# ACS_SchDoc.net
KiCad netlist of a schematic drawn in Altium Designer
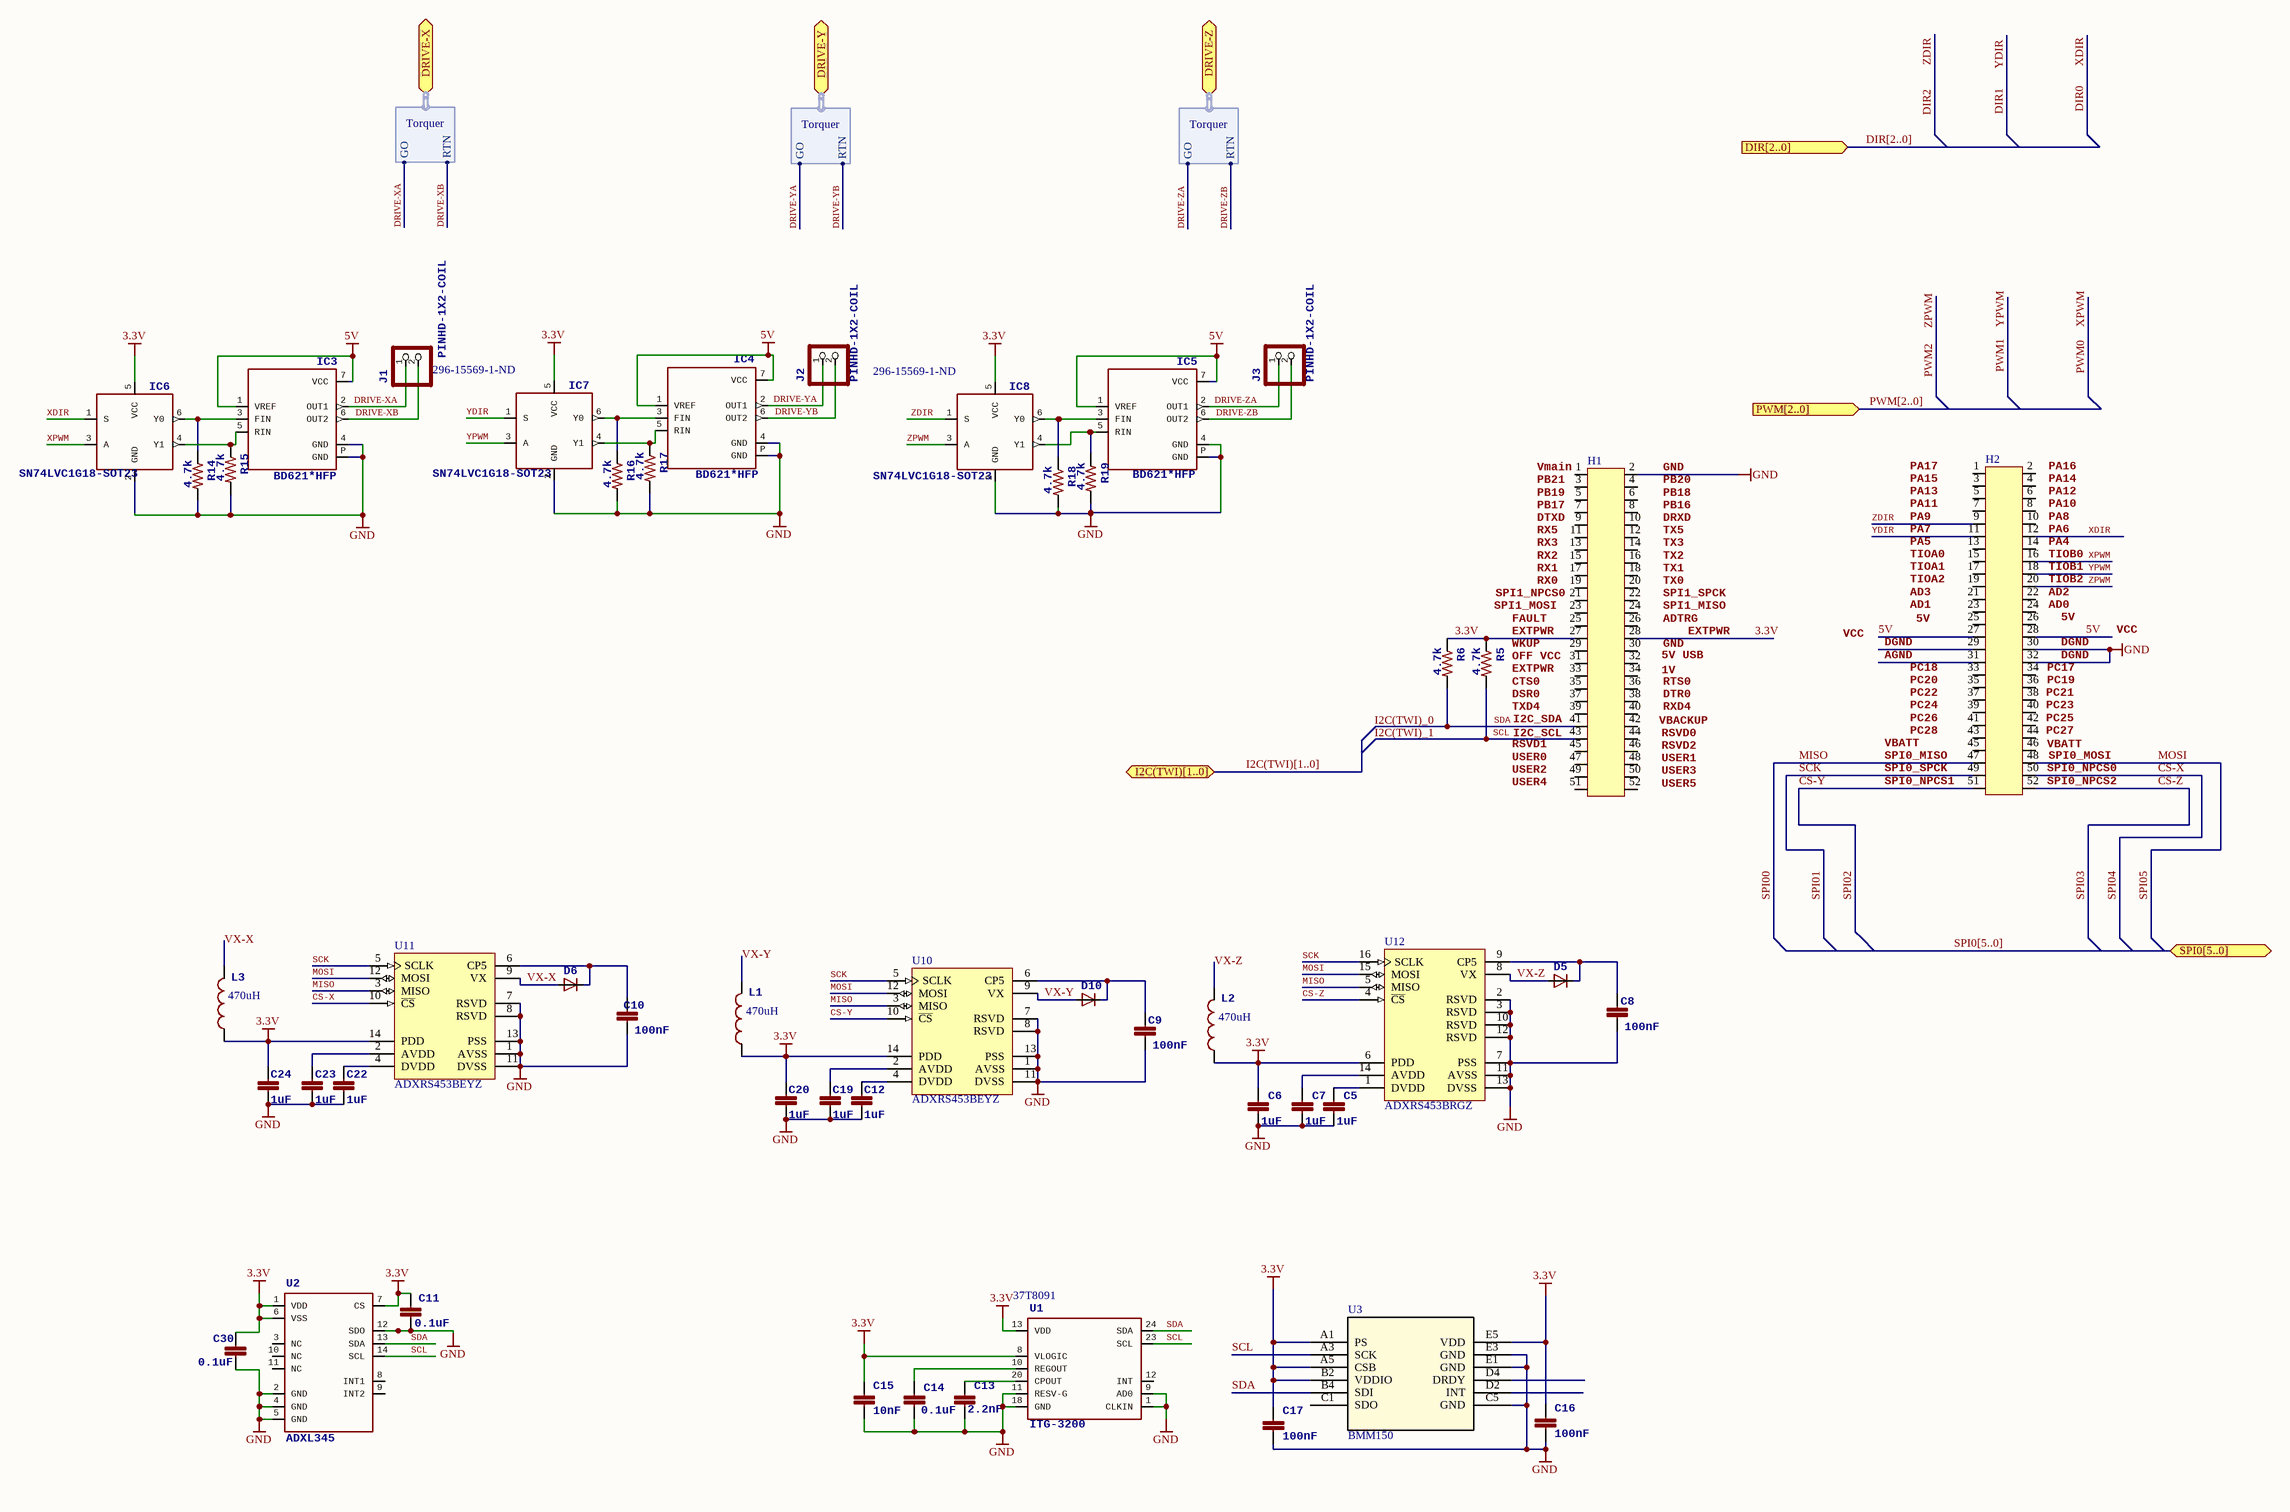
[diagram p0: ACS.SchDoc.SchDoc]

(export (version "E")
  (design (tool "Eeschema 10.0.6"))
  (components
    (comp (ref "C5")
      (value "1uF")
      (footprint "0603-CAP")
      (description "<b>Capacitor</b>\nStandard SMT, and 0.1\", and 0.2\" leaded ceramic capacitors")
      (libsource (lib "") (part "CAPACITOR-0603_1"))
    )
    (comp (ref "C6")
      (value "1uF")
      (footprint "0603-CAP")
      (description "<b>Capacitor</b>\nStandard SMT, and 0.1\", and 0.2\" leaded ceramic capacitors")
      (libsource (lib "") (part "CAPACITOR-0603_1"))
    )
    (comp (ref "C7")
      (value "1uF")
      (footprint "0603-CAP")
      (description "<b>Capacitor</b>\nStandard SMT, and 0.1\", and 0.2\" leaded ceramic capacitors")
      (libsource (lib "") (part "CAPACITOR-0603_1"))
    )
    (comp (ref "C8")
      (value "100nF")
      (footprint "0603-CAP")
      (description "<b>Capacitor</b>\nStandard SMT, and 0.1\", and 0.2\" leaded ceramic capacitors")
      (libsource (lib "urover") (part "CAPACITOR-0603"))
    )
    (comp (ref "C9")
      (value "100nF")
      (footprint "0603-CAP")
      (description "<b>Capacitor</b>\nStandard SMT, and 0.1\", and 0.2\" leaded ceramic capacitors")
      (libsource (lib "urover") (part "CAPACITOR-0603"))
    )
    (comp (ref "C10")
      (value "100nF")
      (footprint "0603-CAP")
      (description "<b>Capacitor</b>\nStandard SMT, and 0.1\", and 0.2\" leaded ceramic capacitors")
      (libsource (lib "urover") (part "CAPACITOR-0603"))
    )
    (comp (ref "C11")
      (value "0.1uF")
      (footprint "0603-CAP")
      (description "<b>Capacitor</b>\nStandard SMT, and 0.1\", and 0.2\" leaded ceramic capacitors")
      (libsource (lib "urover") (part "CAPACITOR-0603"))
    )
    (comp (ref "C12")
      (value "1uF")
      (footprint "0603-CAP")
      (description "<b>Capacitor</b>\nStandard SMT, and 0.1\", and 0.2\" leaded ceramic capacitors")
      (libsource (lib "") (part "CAPACITOR-0603_1"))
    )
    (comp (ref "C13")
      (value "2.2nF")
      (footprint "0603-CAP")
      (description "<b>Capacitor</b>\nStandard SMT, and 0.1\", and 0.2\" leaded ceramic capacitors")
      (libsource (lib "urover") (part "CAPACITOR-0603"))
    )
    (comp (ref "C14")
      (value "0.1uF")
      (footprint "0603-CAP")
      (description "<b>Capacitor</b>\nStandard SMT, and 0.1\", and 0.2\" leaded ceramic capacitors")
      (libsource (lib "urover") (part "CAPACITOR-0603"))
    )
    (comp (ref "C15")
      (value "10nF")
      (footprint "0603-CAP")
      (description "<b>Capacitor</b>\nStandard SMT, and 0.1\", and 0.2\" leaded ceramic capacitors")
      (libsource (lib "urover") (part "CAPACITOR-0603"))
    )
    (comp (ref "C16") (value "100nF") (footprint "0603-CAP") (libsource (lib "ACS") (part "CAPACITOR-0603")))
    (comp (ref "C17") (value "100nF") (footprint "0603-CAP") (libsource (lib "ACS") (part "CAPACITOR-0603")))
    (comp (ref "C19")
      (value "1uF")
      (footprint "0603-CAP")
      (description "<b>Capacitor</b>\nStandard SMT, and 0.1\", and 0.2\" leaded ceramic capacitors")
      (libsource (lib "") (part "CAPACITOR-0603_1"))
    )
    (comp (ref "C20")
      (value "1uF")
      (footprint "0603-CAP")
      (description "<b>Capacitor</b>\nStandard SMT, and 0.1\", and 0.2\" leaded ceramic capacitors")
      (libsource (lib "") (part "CAPACITOR-0603_1"))
    )
    (comp (ref "C22")
      (value "1uF")
      (footprint "0603-CAP")
      (description "<b>Capacitor</b>\nStandard SMT, and 0.1\", and 0.2\" leaded ceramic capacitors")
      (libsource (lib "") (part "CAPACITOR-0603_1"))
    )
    (comp (ref "C23")
      (value "1uF")
      (footprint "0603-CAP")
      (description "<b>Capacitor</b>\nStandard SMT, and 0.1\", and 0.2\" leaded ceramic capacitors")
      (libsource (lib "") (part "CAPACITOR-0603_1"))
    )
    (comp (ref "C24")
      (value "1uF")
      (footprint "0603-CAP")
      (description "<b>Capacitor</b>\nStandard SMT, and 0.1\", and 0.2\" leaded ceramic capacitors")
      (libsource (lib "") (part "CAPACITOR-0603_1"))
    )
    (comp (ref "C30")
      (value "0.1uF")
      (footprint "0603-CAP")
      (description "<b>Capacitor</b>\nStandard SMT, and 0.1\", and 0.2\" leaded ceramic capacitors")
      (libsource (lib "urover") (part "CAPACITOR-0603"))
    )
    (comp (ref "D5")
      (value "<b>Diode</b>\nStandard reverse protection diodes and small signal diodes.")
      (footprint "DIODE-SMA")
      (libsource (lib "urover") (part "DIODE-SMA"))
    )
    (comp (ref "D6")
      (value "<b>Diode</b>\nStandard reverse protection diodes and small signal diodes.")
      (footprint "DIODE-SMA")
      (libsource (lib "urover") (part "DIODE-SMA"))
    )
    (comp (ref "D10")
      (value "<b>Diode</b>\nStandard reverse protection diodes and small signal diodes.")
      (footprint "DIODE-SMA")
      (libsource (lib "urover") (part "DIODE-SMA"))
    )
    (comp (ref "H1")
      (value "H?")
      (footprint "SAMTEC_ESQ_126_39_G_D")
      (description "26X2 header")
      (libsource (lib "SAMTEC_ESQ_126_39_G_D") (part "SAMTEC_ESQ_126_39_G_D"))
    )
    (comp (ref "H2")
      (value "H?")
      (footprint "SAMTEC_ESQ_126_39_G_D")
      (description "26X2 header")
      (libsource (lib "SAMTEC_ESQ_126_39_G_D") (part "SAMTEC_ESQ_126_39_G_D"))
    )
    (comp (ref "IC3")
      (value "BD621*HFP")
      (footprint "HRP7")
      (fields (field (name "MPN") "BD6232HFP-TR"))
      (libsource (lib "urover") (part "BD621*HFP"))
    )
    (comp (ref "IC4")
      (value "BD621*HFP")
      (footprint "HRP7")
      (fields (field (name "MPN") "BD6232HFP-TR"))
      (libsource (lib "urover") (part "BD621*HFP"))
    )
    (comp (ref "IC5")
      (value "BD621*HFP")
      (footprint "HRP7")
      (fields (field (name "MPN") "BD6232HFP-TR"))
      (libsource (lib "urover") (part "BD621*HFP"))
    )
    (comp (ref "IC6")
      (value "SN74LVC1G18-SOT23")
      (footprint "SOT23-6")
      (libsource (lib "urover") (part "SN74LVC1G18-SOT23"))
    )
    (comp (ref "IC7")
      (value "SN74LVC1G18-SOT23")
      (footprint "SOT23-6")
      (fields (field (name "SUPPLIER PART NUMBER 1") "296-15569-1-ND"))
      (libsource (lib "urover") (part "SN74LVC1G18-SOT23"))
    )
    (comp (ref "IC8")
      (value "SN74LVC1G18-SOT23")
      (footprint "SOT23-6")
      (fields (field (name "SUPPLIER PART NUMBER 1") "296-15569-1-ND"))
      (libsource (lib "urover") (part "SN74LVC1G18-SOT23"))
    )
    (comp (ref "J1")
      (value "PINHD-1X2-COIL")
      (footprint "HEADER-1X2-COIL")
      (libsource (lib "urover") (part "PINHD-1X2-COIL"))
    )
    (comp (ref "J2")
      (value "PINHD-1X2-COIL")
      (footprint "HEADER-1X2-COIL")
      (libsource (lib "urover") (part "PINHD-1X2-COIL"))
    )
    (comp (ref "J3")
      (value "PINHD-1X2-COIL")
      (footprint "HEADER-1X2-COIL")
      (libsource (lib "urover") (part "PINHD-1X2-COIL"))
    )
    (comp (ref "L1")
      (value "470uH")
      (footprint "1210")
      (fields (field (name "Comment") "<b>Inductors</b>"))
      (libsource (lib "urover") (part "INDUCTOR-1210_470uH"))
    )
    (comp (ref "L2")
      (value "470uH")
      (footprint "1210")
      (fields (field (name "Comment") "<b>Inductors</b>"))
      (libsource (lib "urover") (part "INDUCTOR-1210_470uH"))
    )
    (comp (ref "L3")
      (value "470uH")
      (footprint "1210")
      (fields (field (name "Comment") "Inductor"))
      (libsource (lib "urover") (part "INDUCTOR-1210_470uH"))
    )
    (comp (ref "R5")
      (value "4.7k")
      (footprint "0603-RES")
      (description "<p><b>Resistor</b></p>\nBasic schematic elements and footprints for resistors.")
      (libsource (lib "urover") (part "RESISTOR-0603"))
    )
    (comp (ref "R6")
      (value "4.7k")
      (footprint "0603-RES")
      (description "<p><b>Resistor</b></p>\nBasic schematic elements and footprints for resistors.")
      (libsource (lib "urover") (part "RESISTOR-0603"))
    )
    (comp (ref "R14")
      (value "4.7k")
      (footprint "0603-RES")
      (description "<p><b>Resistor</b></p>\nBasic schematic elements and footprints for resistors.")
      (libsource (lib "urover") (part "RESISTOR-0603"))
    )
    (comp (ref "R15")
      (value "4.7k")
      (footprint "0603-RES")
      (description "<p><b>Resistor</b></p>\nBasic schematic elements and footprints for resistors.")
      (libsource (lib "urover") (part "RESISTOR-0603"))
    )
    (comp (ref "R16")
      (value "4.7k")
      (footprint "0603-RES")
      (description "<p><b>Resistor</b></p>\nBasic schematic elements and footprints for resistors.")
      (libsource (lib "urover") (part "RESISTOR-0603"))
    )
    (comp (ref "R17")
      (value "4.7k")
      (footprint "0603-RES")
      (description "<p><b>Resistor</b></p>\nBasic schematic elements and footprints for resistors.")
      (libsource (lib "urover") (part "RESISTOR-0603"))
    )
    (comp (ref "R18")
      (value "4.7k")
      (footprint "0603-RES")
      (description "<p><b>Resistor</b></p>\nBasic schematic elements and footprints for resistors.")
      (libsource (lib "urover") (part "RESISTOR-0603"))
    )
    (comp (ref "R19")
      (value "4.7k")
      (footprint "0603-RES")
      (description "<p><b>Resistor</b></p>\nBasic schematic elements and footprints for resistors.")
      (libsource (lib "urover") (part "RESISTOR-0603"))
    )
    (comp (ref "U1")
      (value "ITG-3200")
      (footprint "QFN-24")
      (description "ITG-3200 3-axis gyro, digital output, qfn24 package")
      (fields (field (name "SUPPLIER PART NUMBER 1") "37T8091"))
      (libsource (lib "urover") (part "ITG-3200"))
    )
    (comp (ref "U2") (value "ADXL345") (footprint "LGA14") (libsource (lib "urover") (part "ADXL345")))
    (comp (ref "U3")
      (value "BMM150")
      (footprint "BGA_1590X1590")
      (description "Imported")
      (libsource (lib "BMM150") (part "BMM150"))
    )
    (comp (ref "U10")
      (value "ADXRS453BEYZ")
      (footprint "ADI-EY-14-1_V")
      (description "High Performance, Digital Output Gyroscope with SPI, 77.5 Hz BW, Industrial, 14-pin LCC, Tube")
      (fields (field (name "MANUFACTURER") "Analog Devices"))
      (libsource (lib "Altium Content Vault") (part "ADI-ADXRS453-EY-14-1"))
    )
    (comp (ref "U11")
      (value "ADXRS453BEYZ")
      (footprint "ADI-EY-14-1_V")
      (description "High Performance, Digital Output Gyroscope with SPI, 77.5 Hz BW, Industrial, 14-pin LCC, Tube")
      (fields (field (name "MANUFACTURER") "Analog Devices"))
      (libsource (lib "Altium Content Vault") (part "ADI-ADXRS453-EY-14-1"))
    )
    (comp (ref "U12")
      (value "ADXRS453BRGZ")
      (footprint "ADI-RG-16-1_M")
      (description "High Performance, Digital Output Gyroscope with SPI, 77.5 Hz BW, Industrial, 16-pin SOIC, Tube")
      (fields (field (name "MANUFACTURER") "Analog Devices"))
      (libsource (lib "Altium Content Vault") (part "ADI-ADXRS453-RG-16-1"))
    )
  )
  (nets
    (net (code "4") (name "/DIR0") (class "Default")
      (node (ref "H2") (pin "12") (pinfunction "12_12") (pintype "passive"))
      (node (ref "IC6") (pin "1") (pinfunction "S_1") (pintype "passive"))
    )
    (net (code "5") (name "/DIR1") (class "Default")
      (node (ref "H2") (pin "11") (pinfunction "11_11") (pintype "passive"))
      (node (ref "IC7") (pin "1") (pinfunction "S_1") (pintype "passive"))
    )
    (net (code "6") (name "/DIR2") (class "Default")
      (node (ref "H2") (pin "9") (pinfunction "9_9") (pintype "passive"))
      (node (ref "IC8") (pin "1") (pinfunction "S_1") (pintype "passive"))
    )
    (net (code "8") (name "/DRIVE-XA") (class "Default")
      (node (ref "IC3") (pin "2") (pinfunction "OUT1_2") (pintype "output"))
      (node (ref "J1") (pin "1") (pinfunction "1_1") (pintype "passive"))
    )
    (net (code "9") (name "/DRIVE-XB") (class "Default")
      (node (ref "IC3") (pin "6") (pinfunction "OUT2_6") (pintype "output"))
      (node (ref "J1") (pin "2") (pinfunction "2_2") (pintype "passive"))
    )
    (net (code "10") (name "/DRIVE-YA") (class "Default")
      (node (ref "IC4") (pin "2") (pinfunction "OUT1_2") (pintype "output"))
      (node (ref "J2") (pin "1") (pinfunction "1_1") (pintype "passive"))
    )
    (net (code "11") (name "/DRIVE-YB") (class "Default")
      (node (ref "IC4") (pin "6") (pinfunction "OUT2_6") (pintype "output"))
      (node (ref "J2") (pin "2") (pinfunction "2_2") (pintype "passive"))
    )
    (net (code "12") (name "/DRIVE-ZA") (class "Default")
      (node (ref "IC5") (pin "2") (pinfunction "OUT1_2") (pintype "output"))
      (node (ref "J3") (pin "1") (pinfunction "1_1") (pintype "passive"))
    )
    (net (code "13") (name "/DRIVE-ZB") (class "Default")
      (node (ref "IC5") (pin "6") (pinfunction "OUT2_6") (pintype "output"))
      (node (ref "J3") (pin "2") (pinfunction "2_2") (pintype "passive"))
    )
    (net (code "15") (name "/I2C(TWI)_0") (class "Default")
      (node (ref "H1") (pin "41") (pinfunction "41_41") (pintype "passive"))
      (node (ref "R6") (pin "2") (pinfunction "2_2") (pintype "passive"))
      (node (ref "U1") (pin "24") (pinfunction "SDA_24") (pintype "passive"))
      (node (ref "U2") (pin "13") (pinfunction "SDA_13") (pintype "passive"))
      (node (ref "U3") (pin "B4") (pinfunction "SDI_B4") (pintype "passive"))
    )
    (net (code "16") (name "/I2C(TWI)_1") (class "Default")
      (node (ref "H1") (pin "43") (pinfunction "43_43") (pintype "passive"))
      (node (ref "R5") (pin "2") (pinfunction "2_2") (pintype "passive"))
      (node (ref "U1") (pin "23") (pinfunction "SCL_23") (pintype "passive"))
      (node (ref "U2") (pin "14") (pinfunction "SCL_14") (pintype "passive"))
      (node (ref "U3") (pin "A3") (pinfunction "SCK_A3") (pintype "passive"))
    )
    (net (code "17") (name "/PWM0") (class "Default")
      (node (ref "H2") (pin "16") (pinfunction "16_16") (pintype "passive"))
      (node (ref "IC6") (pin "3") (pinfunction "A_3") (pintype "passive"))
    )
    (net (code "18") (name "/PWM1") (class "Default")
      (node (ref "H2") (pin "18") (pinfunction "18_18") (pintype "passive"))
      (node (ref "IC7") (pin "3") (pinfunction "A_3") (pintype "passive"))
    )
    (net (code "19") (name "/PWM2") (class "Default")
      (node (ref "H2") (pin "20") (pinfunction "20_20") (pintype "passive"))
      (node (ref "IC8") (pin "3") (pinfunction "A_3") (pintype "passive"))
    )
    (net (code "21") (name "/SPI00") (class "Default")
      (node (ref "H2") (pin "47") (pinfunction "47_47") (pintype "passive"))
      (node (ref "U10") (pin "3") (pinfunction "MISO_3") (pintype "bidirectional"))
      (node (ref "U11") (pin "3") (pinfunction "MISO_3") (pintype "bidirectional"))
      (node (ref "U12") (pin "5") (pinfunction "MISO_5") (pintype "bidirectional"))
    )
    (net (code "23") (name "/SPI01") (class "Default")
      (node (ref "H2") (pin "49") (pinfunction "49_49") (pintype "passive"))
      (node (ref "U10") (pin "5") (pinfunction "SCLK_5") (pintype "input"))
      (node (ref "U11") (pin "5") (pinfunction "SCLK_5") (pintype "input"))
      (node (ref "U12") (pin "16") (pinfunction "SCLK_16") (pintype "input"))
    )
    (net (code "24") (name "/SPI02") (class "Default")
      (node (ref "H2") (pin "51") (pinfunction "51_51") (pintype "passive"))
      (node (ref "U10") (pin "10") (pinfunction "~{CS}_10") (pintype "input"))
    )
    (net (code "25") (name "/SPI03") (class "Default")
      (node (ref "H2") (pin "52") (pinfunction "52_52") (pintype "passive"))
      (node (ref "U12") (pin "4") (pinfunction "~{CS}_4") (pintype "input"))
    )
    (net (code "26") (name "/SPI04") (class "Default")
      (node (ref "H2") (pin "50") (pinfunction "50_50") (pintype "passive"))
      (node (ref "U11") (pin "10") (pinfunction "~{CS}_10") (pintype "input"))
    )
    (net (code "27") (name "/SPI05") (class "Default")
      (node (ref "H2") (pin "48") (pinfunction "48_48") (pintype "passive"))
      (node (ref "U10") (pin "12") (pinfunction "MOSI_12") (pintype "bidirectional"))
      (node (ref "U11") (pin "12") (pinfunction "MOSI_12") (pintype "bidirectional"))
      (node (ref "U12") (pin "15") (pinfunction "MOSI_15") (pintype "bidirectional"))
    )
    (net (code "28") (name "/VX-X") (class "Default")
      (node (ref "D6") (pin "A") (pinfunction "A_A") (pintype "passive"))
      (node (ref "L3") (pin "2") (pinfunction "2_2") (pintype "passive"))
      (node (ref "U11") (pin "9") (pinfunction "VX_9") (pintype "power_in"))
    )
    (net (code "29") (name "/VX-Y") (class "Default")
      (node (ref "D10") (pin "A") (pinfunction "A_A") (pintype "passive"))
      (node (ref "L1") (pin "2") (pinfunction "2_2") (pintype "passive"))
      (node (ref "U10") (pin "9") (pinfunction "VX_9") (pintype "power_in"))
    )
    (net (code "30") (name "/VX-Z") (class "Default")
      (node (ref "D5") (pin "A") (pinfunction "A_A") (pintype "passive"))
      (node (ref "L2") (pin "2") (pinfunction "2_2") (pintype "passive"))
      (node (ref "U12") (pin "8") (pinfunction "VX_8") (pintype "power_in"))
    )
    (net (code "32") (name "3.3V") (class "Default")
      (node (ref "C11") (pin "1") (pinfunction "1_1") (pintype "passive"))
      (node (ref "C15") (pin "1") (pinfunction "1_1") (pintype "passive"))
      (node (ref "C16") (pin "1") (pinfunction "1_1") (pintype "passive"))
      (node (ref "C17") (pin "1") (pinfunction "1_1") (pintype "passive"))
      (node (ref "C20") (pin "2") (pinfunction "2_2") (pintype "passive"))
      (node (ref "C24") (pin "2") (pinfunction "2_2") (pintype "passive"))
      (node (ref "C30") (pin "1") (pinfunction "1_1") (pintype "passive"))
      (node (ref "C6") (pin "2") (pinfunction "2_2") (pintype "passive"))
      (node (ref "H1") (pin "27") (pinfunction "27_27") (pintype "passive"))
      (node (ref "H1") (pin "28") (pinfunction "28_28") (pintype "passive"))
      (node (ref "IC6") (pin "5") (pinfunction "VCC_5") (pintype "power_in"))
      (node (ref "IC7") (pin "5") (pinfunction "VCC_5") (pintype "power_in"))
      (node (ref "IC8") (pin "5") (pinfunction "VCC_5") (pintype "power_in"))
      (node (ref "L1") (pin "1") (pinfunction "1_1") (pintype "passive"))
      (node (ref "L2") (pin "1") (pinfunction "1_1") (pintype "passive"))
      (node (ref "L3") (pin "1") (pinfunction "1_1") (pintype "passive"))
      (node (ref "R5") (pin "1") (pinfunction "1_1") (pintype "passive"))
      (node (ref "R6") (pin "1") (pinfunction "1_1") (pintype "passive"))
      (node (ref "U1") (pin "13") (pinfunction "VDD_13") (pintype "passive"))
      (node (ref "U1") (pin "8") (pinfunction "VLOGIC_8") (pintype "passive"))
      (node (ref "U10") (pin "14") (pinfunction "PDD_14") (pintype "power_in"))
      (node (ref "U11") (pin "14") (pinfunction "PDD_14") (pintype "power_in"))
      (node (ref "U12") (pin "6") (pinfunction "PDD_6") (pintype "power_in"))
      (node (ref "U2") (pin "1") (pinfunction "VDD_1") (pintype "passive"))
      (node (ref "U2") (pin "6") (pinfunction "VSS_6") (pintype "passive"))
      (node (ref "U2") (pin "7") (pinfunction "CS_7") (pintype "passive"))
      (node (ref "U3") (pin "A1") (pinfunction "PS_A1") (pintype "passive"))
      (node (ref "U3") (pin "A5") (pinfunction "CSB_A5") (pintype "passive"))
      (node (ref "U3") (pin "B2") (pinfunction "VDDIO_B2") (pintype "passive"))
      (node (ref "U3") (pin "E5") (pinfunction "VDD_E5") (pintype "passive"))
    )
    (net (code "33") (name "5V") (class "Default")
      (node (ref "H2") (pin "27") (pinfunction "27_27") (pintype "passive"))
      (node (ref "H2") (pin "28") (pinfunction "28_28") (pintype "passive"))
      (node (ref "IC3") (pin "1") (pinfunction "VREF_1") (pintype "passive"))
      (node (ref "IC3") (pin "7") (pinfunction "VCC_7") (pintype "power_in"))
      (node (ref "IC4") (pin "1") (pinfunction "VREF_1") (pintype "passive"))
      (node (ref "IC4") (pin "7") (pinfunction "VCC_7") (pintype "power_in"))
      (node (ref "IC5") (pin "1") (pinfunction "VREF_1") (pintype "passive"))
      (node (ref "IC5") (pin "7") (pinfunction "VCC_7") (pintype "power_in"))
    )
    (net (code "34") (name "GND") (class "Default")
      (node (ref "C10") (pin "2") (pinfunction "2_2") (pintype "passive"))
      (node (ref "C11") (pin "2") (pinfunction "2_2") (pintype "passive"))
      (node (ref "C12") (pin "1") (pinfunction "1_1") (pintype "passive"))
      (node (ref "C13") (pin "2") (pinfunction "2_2") (pintype "passive"))
      (node (ref "C14") (pin "2") (pinfunction "2_2") (pintype "passive"))
      (node (ref "C15") (pin "2") (pinfunction "2_2") (pintype "passive"))
      (node (ref "C16") (pin "2") (pinfunction "2_2") (pintype "passive"))
      (node (ref "C17") (pin "2") (pinfunction "2_2") (pintype "passive"))
      (node (ref "C19") (pin "1") (pinfunction "1_1") (pintype "passive"))
      (node (ref "C20") (pin "1") (pinfunction "1_1") (pintype "passive"))
      (node (ref "C22") (pin "1") (pinfunction "1_1") (pintype "passive"))
      (node (ref "C23") (pin "1") (pinfunction "1_1") (pintype "passive"))
      (node (ref "C24") (pin "1") (pinfunction "1_1") (pintype "passive"))
      (node (ref "C30") (pin "2") (pinfunction "2_2") (pintype "passive"))
      (node (ref "C5") (pin "1") (pinfunction "1_1") (pintype "passive"))
      (node (ref "C6") (pin "1") (pinfunction "1_1") (pintype "passive"))
      (node (ref "C7") (pin "1") (pinfunction "1_1") (pintype "passive"))
      (node (ref "C8") (pin "2") (pinfunction "2_2") (pintype "passive"))
      (node (ref "C9") (pin "2") (pinfunction "2_2") (pintype "passive"))
      (node (ref "H1") (pin "2") (pinfunction "2_2") (pintype "passive"))
      (node (ref "H2") (pin "30") (pinfunction "30_30") (pintype "passive"))
      (node (ref "H2") (pin "32") (pinfunction "32_32") (pintype "passive"))
      (node (ref "IC3") (pin "4") (pinfunction "GND_4") (pintype "power_in"))
      (node (ref "IC3") (pin "P") (pinfunction "GND_P") (pintype "power_in"))
      (node (ref "IC4") (pin "4") (pinfunction "GND_4") (pintype "power_in"))
      (node (ref "IC4") (pin "P") (pinfunction "GND_P") (pintype "power_in"))
      (node (ref "IC5") (pin "4") (pinfunction "GND_4") (pintype "power_in"))
      (node (ref "IC5") (pin "P") (pinfunction "GND_P") (pintype "power_in"))
      (node (ref "IC6") (pin "2") (pinfunction "GND_2") (pintype "power_in"))
      (node (ref "IC7") (pin "2") (pinfunction "GND_2") (pintype "power_in"))
      (node (ref "IC8") (pin "2") (pinfunction "GND_2") (pintype "power_in"))
      (node (ref "R14") (pin "2") (pinfunction "2_2") (pintype "passive"))
      (node (ref "R15") (pin "2") (pinfunction "2_2") (pintype "passive"))
      (node (ref "R16") (pin "2") (pinfunction "2_2") (pintype "passive"))
      (node (ref "R17") (pin "2") (pinfunction "2_2") (pintype "passive"))
      (node (ref "R18") (pin "2") (pinfunction "2_2") (pintype "passive"))
      (node (ref "R19") (pin "2") (pinfunction "2_2") (pintype "passive"))
      (node (ref "U1") (pin "1") (pinfunction "CLKIN_1") (pintype "passive"))
      (node (ref "U1") (pin "11") (pinfunction "RESV-G_11") (pintype "passive"))
      (node (ref "U1") (pin "18") (pinfunction "GND_18") (pintype "passive"))
      (node (ref "U1") (pin "9") (pinfunction "AD0_9") (pintype "passive"))
      (node (ref "U10") (pin "1") (pinfunction "AVSS_1") (pintype "power_in"))
      (node (ref "U10") (pin "11") (pinfunction "DVSS_11") (pintype "power_in"))
      (node (ref "U10") (pin "13") (pinfunction "PSS_13") (pintype "power_in"))
      (node (ref "U10") (pin "7") (pinfunction "RSVD_7") (pintype "power_in"))
      (node (ref "U10") (pin "8") (pinfunction "RSVD_8") (pintype "power_in"))
      (node (ref "U11") (pin "1") (pinfunction "AVSS_1") (pintype "power_in"))
      (node (ref "U11") (pin "11") (pinfunction "DVSS_11") (pintype "power_in"))
      (node (ref "U11") (pin "13") (pinfunction "PSS_13") (pintype "power_in"))
      (node (ref "U11") (pin "7") (pinfunction "RSVD_7") (pintype "power_in"))
      (node (ref "U11") (pin "8") (pinfunction "RSVD_8") (pintype "power_in"))
      (node (ref "U12") (pin "10") (pinfunction "RSVD_10") (pintype "power_in"))
      (node (ref "U12") (pin "11") (pinfunction "AVSS_11") (pintype "power_in"))
      (node (ref "U12") (pin "12") (pinfunction "RSVD_12") (pintype "power_in"))
      (node (ref "U12") (pin "13") (pinfunction "DVSS_13") (pintype "power_in"))
      (node (ref "U12") (pin "2") (pinfunction "RSVD_2") (pintype "power_in"))
      (node (ref "U12") (pin "3") (pinfunction "RSVD_3") (pintype "power_in"))
      (node (ref "U12") (pin "7") (pinfunction "PSS_7") (pintype "power_in"))
      (node (ref "U2") (pin "12") (pinfunction "SDO_12") (pintype "passive"))
      (node (ref "U2") (pin "2") (pinfunction "GND_2") (pintype "passive"))
      (node (ref "U2") (pin "4") (pinfunction "GND_4") (pintype "passive"))
      (node (ref "U2") (pin "5") (pinfunction "GND_5") (pintype "passive"))
      (node (ref "U3") (pin "C5") (pinfunction "GND_C5") (pintype "passive"))
      (node (ref "U3") (pin "E1") (pinfunction "GND_E1") (pintype "passive"))
      (node (ref "U3") (pin "E3") (pinfunction "GND_E3") (pintype "passive"))
    )
    (net (code "35") (name "Net-(IC3-FIN)") (class "Default")
      (node (ref "IC3") (pin "3") (pinfunction "FIN_3") (pintype "passive"))
      (node (ref "IC6") (pin "6") (pinfunction "Y0_6") (pintype "output"))
      (node (ref "R14") (pin "1") (pinfunction "1_1") (pintype "passive"))
    )
    (net (code "36") (name "Net-(IC3-RIN)") (class "Default")
      (node (ref "IC3") (pin "5") (pinfunction "RIN_5") (pintype "passive"))
      (node (ref "IC6") (pin "4") (pinfunction "Y1_4") (pintype "output"))
      (node (ref "R15") (pin "1") (pinfunction "1_1") (pintype "passive"))
    )
    (net (code "37") (name "Net-(IC4-FIN)") (class "Default")
      (node (ref "IC4") (pin "3") (pinfunction "FIN_3") (pintype "passive"))
      (node (ref "IC7") (pin "6") (pinfunction "Y0_6") (pintype "output"))
      (node (ref "R16") (pin "1") (pinfunction "1_1") (pintype "passive"))
    )
    (net (code "38") (name "Net-(IC4-RIN)") (class "Default")
      (node (ref "IC4") (pin "5") (pinfunction "RIN_5") (pintype "passive"))
      (node (ref "IC7") (pin "4") (pinfunction "Y1_4") (pintype "output"))
      (node (ref "R17") (pin "1") (pinfunction "1_1") (pintype "passive"))
    )
    (net (code "39") (name "Net-(IC5-FIN)") (class "Default")
      (node (ref "IC5") (pin "3") (pinfunction "FIN_3") (pintype "passive"))
      (node (ref "IC8") (pin "6") (pinfunction "Y0_6") (pintype "output"))
      (node (ref "R18") (pin "1") (pinfunction "1_1") (pintype "passive"))
    )
    (net (code "40") (name "Net-(IC5-RIN)") (class "Default")
      (node (ref "IC5") (pin "5") (pinfunction "RIN_5") (pintype "passive"))
      (node (ref "IC8") (pin "4") (pinfunction "Y1_4") (pintype "output"))
      (node (ref "R19") (pin "1") (pinfunction "1_1") (pintype "passive"))
    )
    (net (code "41") (name "Net-(U1-CPOUT)") (class "Default")
      (node (ref "C13") (pin "1") (pinfunction "1_1") (pintype "passive"))
      (node (ref "U1") (pin "20") (pinfunction "CPOUT_20") (pintype "passive"))
    )
    (net (code "42") (name "Net-(U1-REGOUT)") (class "Default")
      (node (ref "C14") (pin "1") (pinfunction "1_1") (pintype "passive"))
      (node (ref "U1") (pin "10") (pinfunction "REGOUT_10") (pintype "passive"))
    )
    (net (code "43") (name "Net-(U10-AVDD)") (class "Default")
      (node (ref "C19") (pin "2") (pinfunction "2_2") (pintype "passive"))
      (node (ref "U10") (pin "2") (pinfunction "AVDD_2") (pintype "power_in"))
    )
    (net (code "44") (name "Net-(U10-CP5)") (class "Default")
      (node (ref "C9") (pin "1") (pinfunction "1_1") (pintype "passive"))
      (node (ref "D10") (pin "C") (pinfunction "C_C") (pintype "passive"))
      (node (ref "U10") (pin "6") (pinfunction "CP5_6") (pintype "power_in"))
    )
    (net (code "45") (name "Net-(U10-DVDD)") (class "Default")
      (node (ref "C12") (pin "2") (pinfunction "2_2") (pintype "passive"))
      (node (ref "U10") (pin "4") (pinfunction "DVDD_4") (pintype "power_in"))
    )
    (net (code "46") (name "Net-(U11-AVDD)") (class "Default")
      (node (ref "C23") (pin "2") (pinfunction "2_2") (pintype "passive"))
      (node (ref "U11") (pin "2") (pinfunction "AVDD_2") (pintype "power_in"))
    )
    (net (code "47") (name "Net-(U11-CP5)") (class "Default")
      (node (ref "C10") (pin "1") (pinfunction "1_1") (pintype "passive"))
      (node (ref "D6") (pin "C") (pinfunction "C_C") (pintype "passive"))
      (node (ref "U11") (pin "6") (pinfunction "CP5_6") (pintype "power_in"))
    )
    (net (code "48") (name "Net-(U11-DVDD)") (class "Default")
      (node (ref "C22") (pin "2") (pinfunction "2_2") (pintype "passive"))
      (node (ref "U11") (pin "4") (pinfunction "DVDD_4") (pintype "power_in"))
    )
    (net (code "49") (name "Net-(U12-AVDD)") (class "Default")
      (node (ref "C7") (pin "2") (pinfunction "2_2") (pintype "passive"))
      (node (ref "U12") (pin "14") (pinfunction "AVDD_14") (pintype "power_in"))
    )
    (net (code "50") (name "Net-(U12-CP5)") (class "Default")
      (node (ref "C8") (pin "1") (pinfunction "1_1") (pintype "passive"))
      (node (ref "D5") (pin "C") (pinfunction "C_C") (pintype "passive"))
      (node (ref "U12") (pin "9") (pinfunction "CP5_9") (pintype "power_in"))
    )
    (net (code "51") (name "Net-(U12-DVDD)") (class "Default")
      (node (ref "C5") (pin "2") (pinfunction "2_2") (pintype "passive"))
      (node (ref "U12") (pin "1") (pinfunction "DVDD_1") (pintype "power_in"))
    )
    (net (code "52") (name "unconnected-(H1-Pad1)") (class "Default")
      (node (ref "H1") (pin "1") (pinfunction "1_1") (pintype "passive"))
    )
    (net (code "53") (name "unconnected-(H1-Pad3)") (class "Default")
      (node (ref "H1") (pin "3") (pinfunction "3_3") (pintype "passive"))
    )
    (net (code "54") (name "unconnected-(H1-Pad4)") (class "Default")
      (node (ref "H1") (pin "4") (pinfunction "4_4") (pintype "passive"))
    )
    (net (code "55") (name "unconnected-(H1-Pad5)") (class "Default")
      (node (ref "H1") (pin "5") (pinfunction "5_5") (pintype "passive"))
    )
    (net (code "56") (name "unconnected-(H1-Pad6)") (class "Default")
      (node (ref "H1") (pin "6") (pinfunction "6_6") (pintype "passive"))
    )
    (net (code "57") (name "unconnected-(H1-Pad7)") (class "Default")
      (node (ref "H1") (pin "7") (pinfunction "7_7") (pintype "passive"))
    )
    (net (code "58") (name "unconnected-(H1-Pad8)") (class "Default")
      (node (ref "H1") (pin "8") (pinfunction "8_8") (pintype "passive"))
    )
    (net (code "59") (name "unconnected-(H1-Pad9)") (class "Default")
      (node (ref "H1") (pin "9") (pinfunction "9_9") (pintype "passive"))
    )
    (net (code "60") (name "unconnected-(H1-Pad10)") (class "Default")
      (node (ref "H1") (pin "10") (pinfunction "10_10") (pintype "passive"))
    )
    (net (code "61") (name "unconnected-(H1-Pad11)") (class "Default")
      (node (ref "H1") (pin "11") (pinfunction "11_11") (pintype "passive"))
    )
    (net (code "62") (name "unconnected-(H1-Pad12)") (class "Default")
      (node (ref "H1") (pin "12") (pinfunction "12_12") (pintype "passive"))
    )
    (net (code "63") (name "unconnected-(H1-Pad13)") (class "Default")
      (node (ref "H1") (pin "13") (pinfunction "13_13") (pintype "passive"))
    )
    (net (code "64") (name "unconnected-(H1-Pad14)") (class "Default")
      (node (ref "H1") (pin "14") (pinfunction "14_14") (pintype "passive"))
    )
    (net (code "65") (name "unconnected-(H1-Pad15)") (class "Default")
      (node (ref "H1") (pin "15") (pinfunction "15_15") (pintype "passive"))
    )
    (net (code "66") (name "unconnected-(H1-Pad16)") (class "Default")
      (node (ref "H1") (pin "16") (pinfunction "16_16") (pintype "passive"))
    )
    (net (code "67") (name "unconnected-(H1-Pad17)") (class "Default")
      (node (ref "H1") (pin "17") (pinfunction "17_17") (pintype "passive"))
    )
    (net (code "68") (name "unconnected-(H1-Pad18)") (class "Default")
      (node (ref "H1") (pin "18") (pinfunction "18_18") (pintype "passive"))
    )
    (net (code "69") (name "unconnected-(H1-Pad19)") (class "Default")
      (node (ref "H1") (pin "19") (pinfunction "19_19") (pintype "passive"))
    )
    (net (code "70") (name "unconnected-(H1-Pad20)") (class "Default")
      (node (ref "H1") (pin "20") (pinfunction "20_20") (pintype "passive"))
    )
    (net (code "71") (name "unconnected-(H1-Pad21)") (class "Default")
      (node (ref "H1") (pin "21") (pinfunction "21_21") (pintype "passive"))
    )
    (net (code "72") (name "unconnected-(H1-Pad22)") (class "Default")
      (node (ref "H1") (pin "22") (pinfunction "22_22") (pintype "passive"))
    )
    (net (code "73") (name "unconnected-(H1-Pad23)") (class "Default")
      (node (ref "H1") (pin "23") (pinfunction "23_23") (pintype "passive"))
    )
    (net (code "74") (name "unconnected-(H1-Pad24)") (class "Default")
      (node (ref "H1") (pin "24") (pinfunction "24_24") (pintype "passive"))
    )
    (net (code "75") (name "unconnected-(H1-Pad25)") (class "Default")
      (node (ref "H1") (pin "25") (pinfunction "25_25") (pintype "passive"))
    )
    (net (code "76") (name "unconnected-(H1-Pad26)") (class "Default")
      (node (ref "H1") (pin "26") (pinfunction "26_26") (pintype "passive"))
    )
    (net (code "77") (name "unconnected-(H1-Pad29)") (class "Default")
      (node (ref "H1") (pin "29") (pinfunction "29_29") (pintype "passive"))
    )
    (net (code "78") (name "unconnected-(H1-Pad30)") (class "Default")
      (node (ref "H1") (pin "30") (pinfunction "30_30") (pintype "passive"))
    )
    (net (code "79") (name "unconnected-(H1-Pad31)") (class "Default")
      (node (ref "H1") (pin "31") (pinfunction "31_31") (pintype "passive"))
    )
    (net (code "80") (name "unconnected-(H1-Pad32)") (class "Default")
      (node (ref "H1") (pin "32") (pinfunction "32_32") (pintype "passive"))
    )
    (net (code "81") (name "unconnected-(H1-Pad33)") (class "Default")
      (node (ref "H1") (pin "33") (pinfunction "33_33") (pintype "passive"))
    )
    (net (code "82") (name "unconnected-(H1-Pad34)") (class "Default")
      (node (ref "H1") (pin "34") (pinfunction "34_34") (pintype "passive"))
    )
    (net (code "83") (name "unconnected-(H1-Pad35)") (class "Default")
      (node (ref "H1") (pin "35") (pinfunction "35_35") (pintype "passive"))
    )
    (net (code "84") (name "unconnected-(H1-Pad36)") (class "Default")
      (node (ref "H1") (pin "36") (pinfunction "36_36") (pintype "passive"))
    )
    (net (code "85") (name "unconnected-(H1-Pad37)") (class "Default")
      (node (ref "H1") (pin "37") (pinfunction "37_37") (pintype "passive"))
    )
    (net (code "86") (name "unconnected-(H1-Pad38)") (class "Default")
      (node (ref "H1") (pin "38") (pinfunction "38_38") (pintype "passive"))
    )
    (net (code "87") (name "unconnected-(H1-Pad39)") (class "Default")
      (node (ref "H1") (pin "39") (pinfunction "39_39") (pintype "passive"))
    )
    (net (code "88") (name "unconnected-(H1-Pad40)") (class "Default")
      (node (ref "H1") (pin "40") (pinfunction "40_40") (pintype "passive"))
    )
    (net (code "89") (name "unconnected-(H1-Pad42)") (class "Default")
      (node (ref "H1") (pin "42") (pinfunction "42_42") (pintype "passive"))
    )
    (net (code "90") (name "unconnected-(H1-Pad44)") (class "Default")
      (node (ref "H1") (pin "44") (pinfunction "44_44") (pintype "passive"))
    )
    (net (code "91") (name "unconnected-(H1-Pad45)") (class "Default")
      (node (ref "H1") (pin "45") (pinfunction "45_45") (pintype "passive"))
    )
    (net (code "92") (name "unconnected-(H1-Pad46)") (class "Default")
      (node (ref "H1") (pin "46") (pinfunction "46_46") (pintype "passive"))
    )
    (net (code "93") (name "unconnected-(H1-Pad47)") (class "Default")
      (node (ref "H1") (pin "47") (pinfunction "47_47") (pintype "passive"))
    )
    (net (code "94") (name "unconnected-(H1-Pad48)") (class "Default")
      (node (ref "H1") (pin "48") (pinfunction "48_48") (pintype "passive"))
    )
    (net (code "95") (name "unconnected-(H1-Pad49)") (class "Default")
      (node (ref "H1") (pin "49") (pinfunction "49_49") (pintype "passive"))
    )
    (net (code "96") (name "unconnected-(H1-Pad50)") (class "Default")
      (node (ref "H1") (pin "50") (pinfunction "50_50") (pintype "passive"))
    )
    (net (code "97") (name "unconnected-(H1-Pad51)") (class "Default")
      (node (ref "H1") (pin "51") (pinfunction "51_51") (pintype "passive"))
    )
    (net (code "98") (name "unconnected-(H1-Pad52)") (class "Default")
      (node (ref "H1") (pin "52") (pinfunction "52_52") (pintype "passive"))
    )
    (net (code "99") (name "unconnected-(H2-Pad1)") (class "Default")
      (node (ref "H2") (pin "1") (pinfunction "1_1") (pintype "passive"))
    )
    (net (code "100") (name "unconnected-(H2-Pad2)") (class "Default")
      (node (ref "H2") (pin "2") (pinfunction "2_2") (pintype "passive"))
    )
    (net (code "101") (name "unconnected-(H2-Pad3)") (class "Default")
      (node (ref "H2") (pin "3") (pinfunction "3_3") (pintype "passive"))
    )
    (net (code "102") (name "unconnected-(H2-Pad4)") (class "Default")
      (node (ref "H2") (pin "4") (pinfunction "4_4") (pintype "passive"))
    )
    (net (code "103") (name "unconnected-(H2-Pad5)") (class "Default")
      (node (ref "H2") (pin "5") (pinfunction "5_5") (pintype "passive"))
    )
    (net (code "104") (name "unconnected-(H2-Pad6)") (class "Default")
      (node (ref "H2") (pin "6") (pinfunction "6_6") (pintype "passive"))
    )
    (net (code "105") (name "unconnected-(H2-Pad7)") (class "Default")
      (node (ref "H2") (pin "7") (pinfunction "7_7") (pintype "passive"))
    )
    (net (code "106") (name "unconnected-(H2-Pad8)") (class "Default")
      (node (ref "H2") (pin "8") (pinfunction "8_8") (pintype "passive"))
    )
    (net (code "107") (name "unconnected-(H2-Pad10)") (class "Default")
      (node (ref "H2") (pin "10") (pinfunction "10_10") (pintype "passive"))
    )
    (net (code "108") (name "unconnected-(H2-Pad13)") (class "Default")
      (node (ref "H2") (pin "13") (pinfunction "13_13") (pintype "passive"))
    )
    (net (code "109") (name "unconnected-(H2-Pad14)") (class "Default")
      (node (ref "H2") (pin "14") (pinfunction "14_14") (pintype "passive"))
    )
    (net (code "110") (name "unconnected-(H2-Pad15)") (class "Default")
      (node (ref "H2") (pin "15") (pinfunction "15_15") (pintype "passive"))
    )
    (net (code "111") (name "unconnected-(H2-Pad17)") (class "Default")
      (node (ref "H2") (pin "17") (pinfunction "17_17") (pintype "passive"))
    )
    (net (code "112") (name "unconnected-(H2-Pad19)") (class "Default")
      (node (ref "H2") (pin "19") (pinfunction "19_19") (pintype "passive"))
    )
    (net (code "113") (name "unconnected-(H2-Pad21)") (class "Default")
      (node (ref "H2") (pin "21") (pinfunction "21_21") (pintype "passive"))
    )
    (net (code "114") (name "unconnected-(H2-Pad22)") (class "Default")
      (node (ref "H2") (pin "22") (pinfunction "22_22") (pintype "passive"))
    )
    (net (code "115") (name "unconnected-(H2-Pad23)") (class "Default")
      (node (ref "H2") (pin "23") (pinfunction "23_23") (pintype "passive"))
    )
    (net (code "116") (name "unconnected-(H2-Pad24)") (class "Default")
      (node (ref "H2") (pin "24") (pinfunction "24_24") (pintype "passive"))
    )
    (net (code "117") (name "unconnected-(H2-Pad25)") (class "Default")
      (node (ref "H2") (pin "25") (pinfunction "25_25") (pintype "passive"))
    )
    (net (code "118") (name "unconnected-(H2-Pad26)") (class "Default")
      (node (ref "H2") (pin "26") (pinfunction "26_26") (pintype "passive"))
    )
    (net (code "119") (name "unconnected-(H2-Pad29)") (class "Default")
      (node (ref "H2") (pin "29") (pinfunction "29_29") (pintype "passive"))
    )
    (net (code "120") (name "unconnected-(H2-Pad31)") (class "Default")
      (node (ref "H2") (pin "31") (pinfunction "31_31") (pintype "passive"))
    )
    (net (code "121") (name "unconnected-(H2-Pad33)") (class "Default")
      (node (ref "H2") (pin "33") (pinfunction "33_33") (pintype "passive"))
    )
    (net (code "122") (name "unconnected-(H2-Pad34)") (class "Default")
      (node (ref "H2") (pin "34") (pinfunction "34_34") (pintype "passive"))
    )
    (net (code "123") (name "unconnected-(H2-Pad35)") (class "Default")
      (node (ref "H2") (pin "35") (pinfunction "35_35") (pintype "passive"))
    )
    (net (code "124") (name "unconnected-(H2-Pad36)") (class "Default")
      (node (ref "H2") (pin "36") (pinfunction "36_36") (pintype "passive"))
    )
    (net (code "125") (name "unconnected-(H2-Pad37)") (class "Default")
      (node (ref "H2") (pin "37") (pinfunction "37_37") (pintype "passive"))
    )
    (net (code "126") (name "unconnected-(H2-Pad38)") (class "Default")
      (node (ref "H2") (pin "38") (pinfunction "38_38") (pintype "passive"))
    )
    (net (code "127") (name "unconnected-(H2-Pad39)") (class "Default")
      (node (ref "H2") (pin "39") (pinfunction "39_39") (pintype "passive"))
    )
    (net (code "128") (name "unconnected-(H2-Pad40)") (class "Default")
      (node (ref "H2") (pin "40") (pinfunction "40_40") (pintype "passive"))
    )
    (net (code "129") (name "unconnected-(H2-Pad41)") (class "Default")
      (node (ref "H2") (pin "41") (pinfunction "41_41") (pintype "passive"))
    )
    (net (code "130") (name "unconnected-(H2-Pad42)") (class "Default")
      (node (ref "H2") (pin "42") (pinfunction "42_42") (pintype "passive"))
    )
    (net (code "131") (name "unconnected-(H2-Pad43)") (class "Default")
      (node (ref "H2") (pin "43") (pinfunction "43_43") (pintype "passive"))
    )
    (net (code "132") (name "unconnected-(H2-Pad44)") (class "Default")
      (node (ref "H2") (pin "44") (pinfunction "44_44") (pintype "passive"))
    )
    (net (code "133") (name "unconnected-(H2-Pad45)") (class "Default")
      (node (ref "H2") (pin "45") (pinfunction "45_45") (pintype "passive"))
    )
    (net (code "134") (name "unconnected-(H2-Pad46)") (class "Default")
      (node (ref "H2") (pin "46") (pinfunction "46_46") (pintype "passive"))
    )
    (net (code "135") (name "unconnected-(U1-INT-Pad12)") (class "Default")
      (node (ref "U1") (pin "12") (pinfunction "INT_12") (pintype "passive"))
    )
    (net (code "136") (name "unconnected-(U2-INT1-Pad8)") (class "Default")
      (node (ref "U2") (pin "8") (pinfunction "INT1_8") (pintype "passive"))
    )
    (net (code "137") (name "unconnected-(U2-INT2-Pad9)") (class "Default")
      (node (ref "U2") (pin "9") (pinfunction "INT2_9") (pintype "passive"))
    )
    (net (code "138") (name "unconnected-(U2-NC-Pad3)") (class "Default")
      (node (ref "U2") (pin "3") (pinfunction "NC_3") (pintype "passive"))
    )
    (net (code "139") (name "unconnected-(U2-NC-Pad10)") (class "Default")
      (node (ref "U2") (pin "10") (pinfunction "NC_10") (pintype "passive"))
    )
    (net (code "140") (name "unconnected-(U2-NC-Pad11)") (class "Default")
      (node (ref "U2") (pin "11") (pinfunction "NC_11") (pintype "passive"))
    )
    (net (code "141") (name "unconnected-(U3-DRDY-PadD4)") (class "Default")
      (node (ref "U3") (pin "D4") (pinfunction "DRDY_D4") (pintype "passive"))
    )
    (net (code "142") (name "unconnected-(U3-INT-PadD2)") (class "Default")
      (node (ref "U3") (pin "D2") (pinfunction "INT_D2") (pintype "passive"))
    )
    (net (code "143") (name "unconnected-(U3-SDO-PadC1)") (class "Default")
      (node (ref "U3") (pin "C1") (pinfunction "SDO_C1") (pintype "passive"))
    )
  )
)
